# AUX_OPAMP.net
KiCad netlist of a schematic drawn in Altium Designer
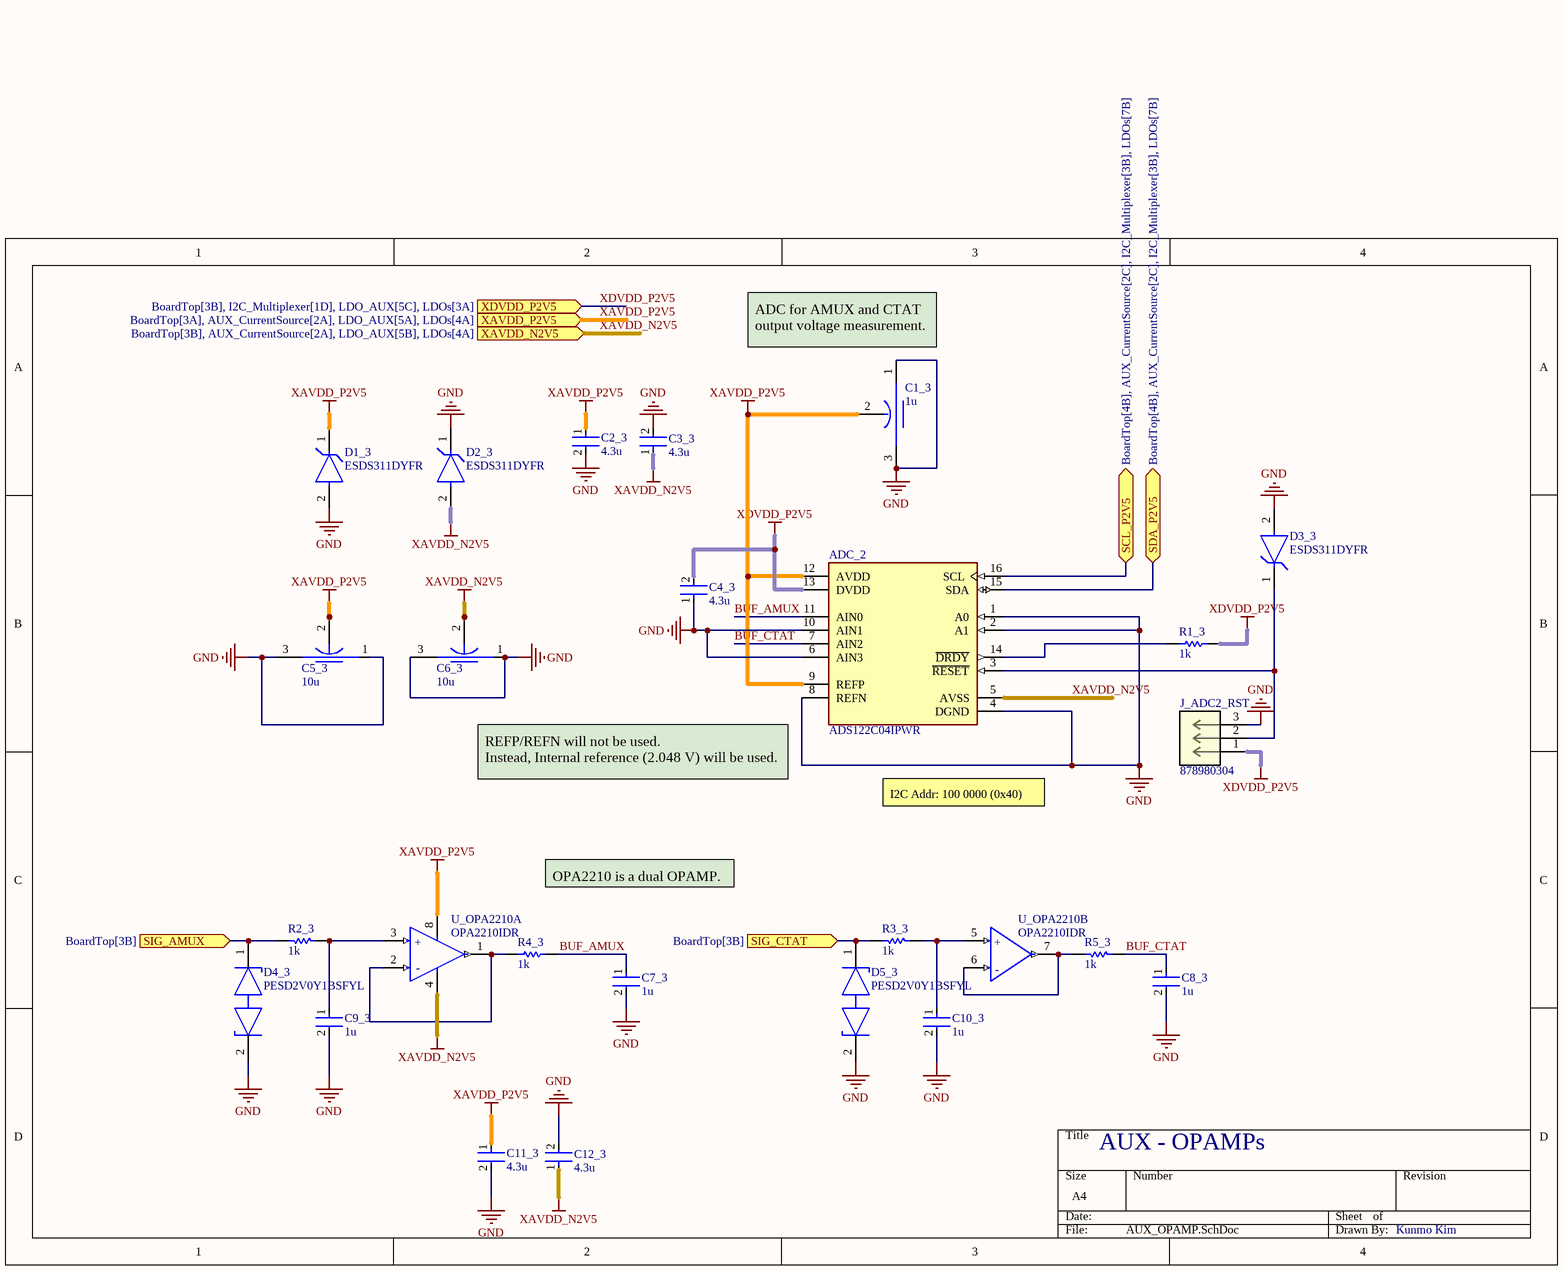
[diagram p0: AUX_OPAMP.SchDoc]

(export (version "E")
  (design (tool "Eeschema 10.0.6"))
  (components
    (comp (ref "ADC_2")
      (value "ADS122C04IPWR")
      (footprint "FP-PW0016A-IPC_C")
      (description "IC ADC 24BIT SIGMA-DELTA 16TSSOP")
      (libsource (lib "Altium Content Vault") (part "c28109da439a1fe3ed8269d84f6cd58"))
    )
    (comp (ref "C1_3")
      (value "1u")
      (footprint "PCBComponent_1")
      (description "0402(1005M) 4V 1.0UF +/- 20% 3 T")
      (fields (field (name "TOLERANCE") "20%"))
      (libsource (lib "NFM15HC105D0G3D") (part "CMP-06053-000757-1"))
    )
    (comp (ref "C2_3")
      (value "4.3u")
      (footprint "FP-LLL1U4-0_05-MFG")
      (description "Cap Ceramic Monolithic 4.3uF 20% 4V X5R 15% 02404 (0610M)")
      (fields (field (name "TOLERANCE") "20%"))
      (libsource (lib "Altium Content Vault") (part "b4654b650e69147ec39a6b967a45e02"))
    )
    (comp (ref "C3_3")
      (value "4.3u")
      (footprint "FP-LLL1U4-0_05-MFG")
      (description "Cap Ceramic Monolithic 4.3uF 20% 4V X5R 15% 02404 (0610M)")
      (fields (field (name "TOLERANCE") "20%"))
      (libsource (lib "Altium Content Vault") (part "b4654b650e69147ec39a6b967a45e02"))
    )
    (comp (ref "C4_3")
      (value "4.3u")
      (footprint "FP-LLL1U4-0_05-MFG")
      (description "Cap Ceramic Monolithic 4.3uF 20% 4V X5R 15% 02404 (0610M)")
      (fields (field (name "TOLERANCE") "20%"))
      (libsource (lib "Altium Content Vault") (part "b4654b650e69147ec39a6b967a45e02"))
    )
    (comp (ref "C5_3")
      (value "10u")
      (footprint "FP-NFM15-0_2-MFG")
      (description "CAP FEEDTHRU")
      (libsource (lib "Altium Content Vault") (part "0d6e7657c98936515f4dd3c3b322889"))
    )
    (comp (ref "C6_3")
      (value "10u")
      (footprint "FP-NFM15-0_2-MFG")
      (description "CAP FEEDTHRU")
      (libsource (lib "Altium Content Vault") (part "0d6e7657c98936515f4dd3c3b322889"))
    )
    (comp (ref "C7_3")
      (value "1u")
      (footprint "FP-C0402C105K8PACTU-IPC_A")
      (description "CAP CER 1UF 10V X5R 0402")
      (fields (field (name "VOLTAGE") "10V") (field (name "TOLERANCE") "10%"))
      (libsource (lib "KEMET_1uF_0402_cap") (part "CMP-2008-02081-2"))
    )
    (comp (ref "C8_3")
      (value "1u")
      (footprint "FP-C0402C105K8PACTU-IPC_A")
      (description "CAP CER 1UF 10V X5R 0402")
      (fields (field (name "VOLTAGE") "10V") (field (name "TOLERANCE") "10%"))
      (libsource (lib "KEMET_1uF_0402_cap") (part "CMP-2008-02081-2"))
    )
    (comp (ref "C9_3")
      (value "1u")
      (footprint "FP-C0402C105K8PACTU-IPC_A")
      (description "CAP CER 1UF 10V X5R 0402")
      (fields (field (name "VOLTAGE") "10V") (field (name "TOLERANCE") "10%"))
      (libsource (lib "KEMET_1uF_0402_cap") (part "CMP-2008-02081-2"))
    )
    (comp (ref "C10_3")
      (value "1u")
      (footprint "FP-C0402C105K8PACTU-IPC_A")
      (description "CAP CER 1UF 10V X5R 0402")
      (fields (field (name "VOLTAGE") "10V") (field (name "TOLERANCE") "10%"))
      (libsource (lib "KEMET_1uF_0402_cap") (part "CMP-2008-02081-2"))
    )
    (comp (ref "C11_3")
      (value "4.3u")
      (footprint "FP-LLL1U4-0_05-MFG")
      (description "Cap Ceramic Monolithic 4.3uF 20% 4V X5R 15% 02404 (0610M)")
      (fields (field (name "TOLERANCE") "20%"))
      (libsource (lib "Altium Content Vault") (part "b4654b650e69147ec39a6b967a45e02"))
    )
    (comp (ref "C12_3")
      (value "4.3u")
      (footprint "FP-LLL1U4-0_05-MFG")
      (description "Cap Ceramic Monolithic 4.3uF 20% 4V X5R 15% 02404 (0610M)")
      (fields (field (name "TOLERANCE") "20%"))
      (libsource (lib "Altium Content Vault") (part "b4654b650e69147ec39a6b967a45e02"))
    )
    (comp (ref "D1_3")
      (value "ESDS311DYFR")
      (footprint "FP-DYF0002A-IPC_B")
      (libsource (lib "Altium Content Vault") (part "d0b9196d99f40cb8efe007e69fff614"))
    )
    (comp (ref "D2_3")
      (value "ESDS311DYFR")
      (footprint "FP-DYF0002A-IPC_B")
      (libsource (lib "Altium Content Vault") (part "d0b9196d99f40cb8efe007e69fff614"))
    )
    (comp (ref "D3_3")
      (value "ESDS311DYFR")
      (footprint "FP-DYF0002A-IPC_B")
      (libsource (lib "Altium Content Vault") (part "d0b9196d99f40cb8efe007e69fff614"))
    )
    (comp (ref "D4_3")
      (value "PESD2V0Y1BSFYL")
      (footprint "FP-SOD962-2-MFG")
      (description "TVS DIODE 2VWM 3VC DSN0603-2")
      (libsource (lib "Altium Content Vault") (part "3b819f4016a974b32db02c4901e5706"))
    )
    (comp (ref "D5_3")
      (value "PESD2V0Y1BSFYL")
      (footprint "FP-SOD962-2-MFG")
      (description "TVS DIODE 2VWM 3VC DSN0603-2")
      (libsource (lib "Altium Content Vault") (part "3b819f4016a974b32db02c4901e5706"))
    )
    (comp (ref "J_ADC2_RST")
      (value "878980304")
      (footprint "CONN03_87898_M-5p84_MOL")
      (description "No Description Available")
      (libsource (lib "878980304") (part "878980304"))
    )
    (comp (ref "R1_3")
      (value "1k")
      (footprint "RESC1608X55X30LL15T15")
      (fields (field (name "PART NUMBER") "ERJ-3EKF1001V") (field (name "MANUFACTURER") "Panasonic"))
      (libsource (lib "res_0603_1k") (part "CMP-2000-00180-1"))
    )
    (comp (ref "R2_3")
      (value "1k")
      (footprint "RESC1608X55X30LL15T15")
      (fields (field (name "PART NUMBER") "ERJ-3EKF1001V") (field (name "MANUFACTURER") "Panasonic"))
      (libsource (lib "res_0603_1k") (part "CMP-2000-00180-1"))
    )
    (comp (ref "R3_3")
      (value "1k")
      (footprint "RESC1608X55X30LL15T15")
      (fields (field (name "PART NUMBER") "ERJ-3EKF1001V") (field (name "MANUFACTURER") "Panasonic"))
      (libsource (lib "res_0603_1k") (part "CMP-2000-00180-1"))
    )
    (comp (ref "R4_3")
      (value "1k")
      (footprint "RESC1608X55X30LL15T15")
      (fields (field (name "PART NUMBER") "ERJ-3EKF1001V") (field (name "MANUFACTURER") "Panasonic"))
      (libsource (lib "res_0603_1k") (part "CMP-2000-00180-1"))
    )
    (comp (ref "R5_3")
      (value "1k")
      (footprint "RESC1608X55X30LL15T15")
      (fields (field (name "PART NUMBER") "ERJ-3EKF1001V") (field (name "MANUFACTURER") "Panasonic"))
      (libsource (lib "res_0603_1k") (part "CMP-2000-00180-1"))
    )
    (comp (ref "U_OPA2210")
      (value "OPA2210IDR")
      (footprint "FP-D0008A-MFG")
      (description "IC OP-AMP")
      (fields
        (field (name "OCTOPART") "https://octopart.com/opa2210idr-texas+instruments-105815795")
        (field (name "MANUFACTURER") "Texas Instruments")
      )
      (libsource (lib "Altium Content Vault") (part "e8c52d48d03680a0ba04c611cf3b55d"))
    )
  )
  (nets
    (net (code "1") (name "/BUF_AMUX") (class "Default")
      (node (ref "ADC_2") (pin "11") (pinfunction "AIN0_11") (pintype "passive"))
      (node (ref "C7_3") (pin "1") (pinfunction "1_1") (pintype "passive"))
      (node (ref "R4_3") (pin "1") (pinfunction "1_1") (pintype "passive"))
    )
    (net (code "2") (name "/BUF_CTAT") (class "Default")
      (node (ref "ADC_2") (pin "7") (pinfunction "AIN2_7") (pintype "passive"))
      (node (ref "C8_3") (pin "1") (pinfunction "1_1") (pintype "passive"))
      (node (ref "R5_3") (pin "2") (pinfunction "2_2") (pintype "passive"))
    )
    (net (code "3") (name "/SCL_P2V5") (class "Default")
      (node (ref "ADC_2") (pin "16") (pinfunction "SCL_16") (pintype "input"))
    )
    (net (code "4") (name "/SDA_P2V5") (class "Default")
      (node (ref "ADC_2") (pin "15") (pinfunction "SDA_15") (pintype "bidirectional"))
    )
    (net (code "5") (name "/SIG_AMUX") (class "Default")
      (node (ref "D4_3") (pin "1") (pinfunction "K1_1") (pintype "passive"))
      (node (ref "R2_3") (pin "1") (pinfunction "1_1") (pintype "passive"))
    )
    (net (code "6") (name "/SIG_CTAT") (class "Default")
      (node (ref "D5_3") (pin "1") (pinfunction "K1_1") (pintype "passive"))
      (node (ref "R3_3") (pin "1") (pinfunction "1_1") (pintype "passive"))
    )
    (net (code "7") (name "GND") (class "Default")
      (node (ref "ADC_2") (pin "1") (pinfunction "A0_1") (pintype "input"))
      (node (ref "ADC_2") (pin "10") (pinfunction "AIN1_10") (pintype "passive"))
      (node (ref "ADC_2") (pin "2") (pinfunction "A1_2") (pintype "input"))
      (node (ref "ADC_2") (pin "4") (pinfunction "DGND_4") (pintype "power_in"))
      (node (ref "ADC_2") (pin "6") (pinfunction "AIN3_6") (pintype "passive"))
      (node (ref "ADC_2") (pin "8") (pinfunction "REFN_8") (pintype "passive"))
      (node (ref "C10_3") (pin "2") (pinfunction "2_2") (pintype "passive"))
      (node (ref "C11_3") (pin "2") (pinfunction "2_2") (pintype "passive"))
      (node (ref "C12_3") (pin "2") (pinfunction "2_2") (pintype "passive"))
      (node (ref "C1_3") (pin "1") (pinfunction "Input_1") (pintype "passive"))
      (node (ref "C1_3") (pin "3") (pinfunction "Output_3") (pintype "passive"))
      (node (ref "C2_3") (pin "2") (pinfunction "2_2") (pintype "passive"))
      (node (ref "C3_3") (pin "2") (pinfunction "2_2") (pintype "passive"))
      (node (ref "C4_3") (pin "1") (pinfunction "1_1") (pintype "passive"))
      (node (ref "C5_3") (pin "1") (pinfunction "Input_1") (pintype "passive"))
      (node (ref "C5_3") (pin "3") (pinfunction "Output_3") (pintype "passive"))
      (node (ref "C6_3") (pin "1") (pinfunction "Input_1") (pintype "passive"))
      (node (ref "C6_3") (pin "3") (pinfunction "Output_3") (pintype "passive"))
      (node (ref "C7_3") (pin "2") (pinfunction "2_2") (pintype "passive"))
      (node (ref "C8_3") (pin "2") (pinfunction "2_2") (pintype "passive"))
      (node (ref "C9_3") (pin "2") (pinfunction "2_2") (pintype "passive"))
      (node (ref "D1_3") (pin "2") (pinfunction "GND_2") (pintype "power_in"))
      (node (ref "D2_3") (pin "1") (pinfunction "I/O_1") (pintype "passive"))
      (node (ref "D3_3") (pin "2") (pinfunction "GND_2") (pintype "power_in"))
      (node (ref "D4_3") (pin "2") (pinfunction "K2_2") (pintype "passive"))
      (node (ref "D5_3") (pin "2") (pinfunction "K2_2") (pintype "passive"))
      (node (ref "J_ADC2_RST") (pin "3") (pinfunction "3_3") (pintype "passive"))
    )
    (net (code "8") (name "Net-(ADC_2-~{DRDY})") (class "Default")
      (node (ref "ADC_2") (pin "14") (pinfunction "~{DRDY}_14") (pintype "output"))
      (node (ref "R1_3") (pin "2") (pinfunction "2_2") (pintype "passive"))
    )
    (net (code "9") (name "Net-(ADC_2-~{RESET})") (class "Default")
      (node (ref "ADC_2") (pin "3") (pinfunction "~{RESET}_3") (pintype "input"))
      (node (ref "D3_3") (pin "1") (pinfunction "I/O_1") (pintype "passive"))
      (node (ref "J_ADC2_RST") (pin "2") (pinfunction "2_2") (pintype "passive"))
    )
    (net (code "10") (name "Net-(U_OPA2210A-+IN_A)") (class "Default")
      (node (ref "C9_3") (pin "1") (pinfunction "1_1") (pintype "passive"))
      (node (ref "R2_3") (pin "2") (pinfunction "2_2") (pintype "passive"))
      (node (ref "U_OPA2210") (pin "3") (pinfunction "+IN_A_3") (pintype "input"))
    )
    (net (code "11") (name "Net-(U_OPA2210A--IN_A)") (class "Default")
      (node (ref "R4_3") (pin "2") (pinfunction "2_2") (pintype "passive"))
      (node (ref "U_OPA2210") (pin "1") (pinfunction "OUT_A_1") (pintype "output"))
      (node (ref "U_OPA2210") (pin "2") (pinfunction "-IN_A_2") (pintype "input"))
    )
    (net (code "12") (name "Net-(U_OPA2210B-+IN_B)") (class "Default")
      (node (ref "C10_3") (pin "1") (pinfunction "1_1") (pintype "passive"))
      (node (ref "R3_3") (pin "2") (pinfunction "2_2") (pintype "passive"))
      (node (ref "U_OPA2210") (pin "5") (pinfunction "+IN_B_5") (pintype "input"))
    )
    (net (code "13") (name "Net-(U_OPA2210B--IN_B)") (class "Default")
      (node (ref "R5_3") (pin "1") (pinfunction "1_1") (pintype "passive"))
      (node (ref "U_OPA2210") (pin "6") (pinfunction "-IN_B_6") (pintype "input"))
      (node (ref "U_OPA2210") (pin "7") (pinfunction "OUT_B_7") (pintype "output"))
    )
    (net (code "14") (name "XAVDD_N2V5") (class "Default")
      (node (ref "ADC_2") (pin "5") (pinfunction "AVSS_5") (pintype "power_in"))
      (node (ref "C12_3") (pin "1") (pinfunction "1_1") (pintype "passive"))
      (node (ref "C3_3") (pin "1") (pinfunction "1_1") (pintype "passive"))
      (node (ref "C6_3") (pin "2") (pinfunction "GND_2") (pintype "passive"))
      (node (ref "D2_3") (pin "2") (pinfunction "GND_2") (pintype "power_in"))
      (node (ref "U_OPA2210") (pin "4") (pinfunction "V-_4") (pintype "power_in"))
    )
    (net (code "15") (name "XAVDD_P2V5") (class "Default")
      (node (ref "ADC_2") (pin "12") (pinfunction "AVDD_12") (pintype "power_in"))
      (node (ref "ADC_2") (pin "9") (pinfunction "REFP_9") (pintype "passive"))
      (node (ref "C11_3") (pin "1") (pinfunction "1_1") (pintype "passive"))
      (node (ref "C1_3") (pin "2") (pinfunction "GND_2") (pintype "passive"))
      (node (ref "C2_3") (pin "1") (pinfunction "1_1") (pintype "passive"))
      (node (ref "C5_3") (pin "2") (pinfunction "GND_2") (pintype "passive"))
      (node (ref "D1_3") (pin "1") (pinfunction "I/O_1") (pintype "passive"))
      (node (ref "U_OPA2210") (pin "8") (pinfunction "V+_8") (pintype "power_in"))
    )
    (net (code "16") (name "XDVDD_P2V5") (class "Default")
      (node (ref "ADC_2") (pin "13") (pinfunction "DVDD_13") (pintype "power_in"))
      (node (ref "C4_3") (pin "2") (pinfunction "2_2") (pintype "passive"))
      (node (ref "J_ADC2_RST") (pin "1") (pinfunction "1_1") (pintype "passive"))
      (node (ref "R1_3") (pin "1") (pinfunction "1_1") (pintype "passive"))
    )
  )
)
